# HIM.net
KiCad netlist of a schematic drawn in Altium Designer
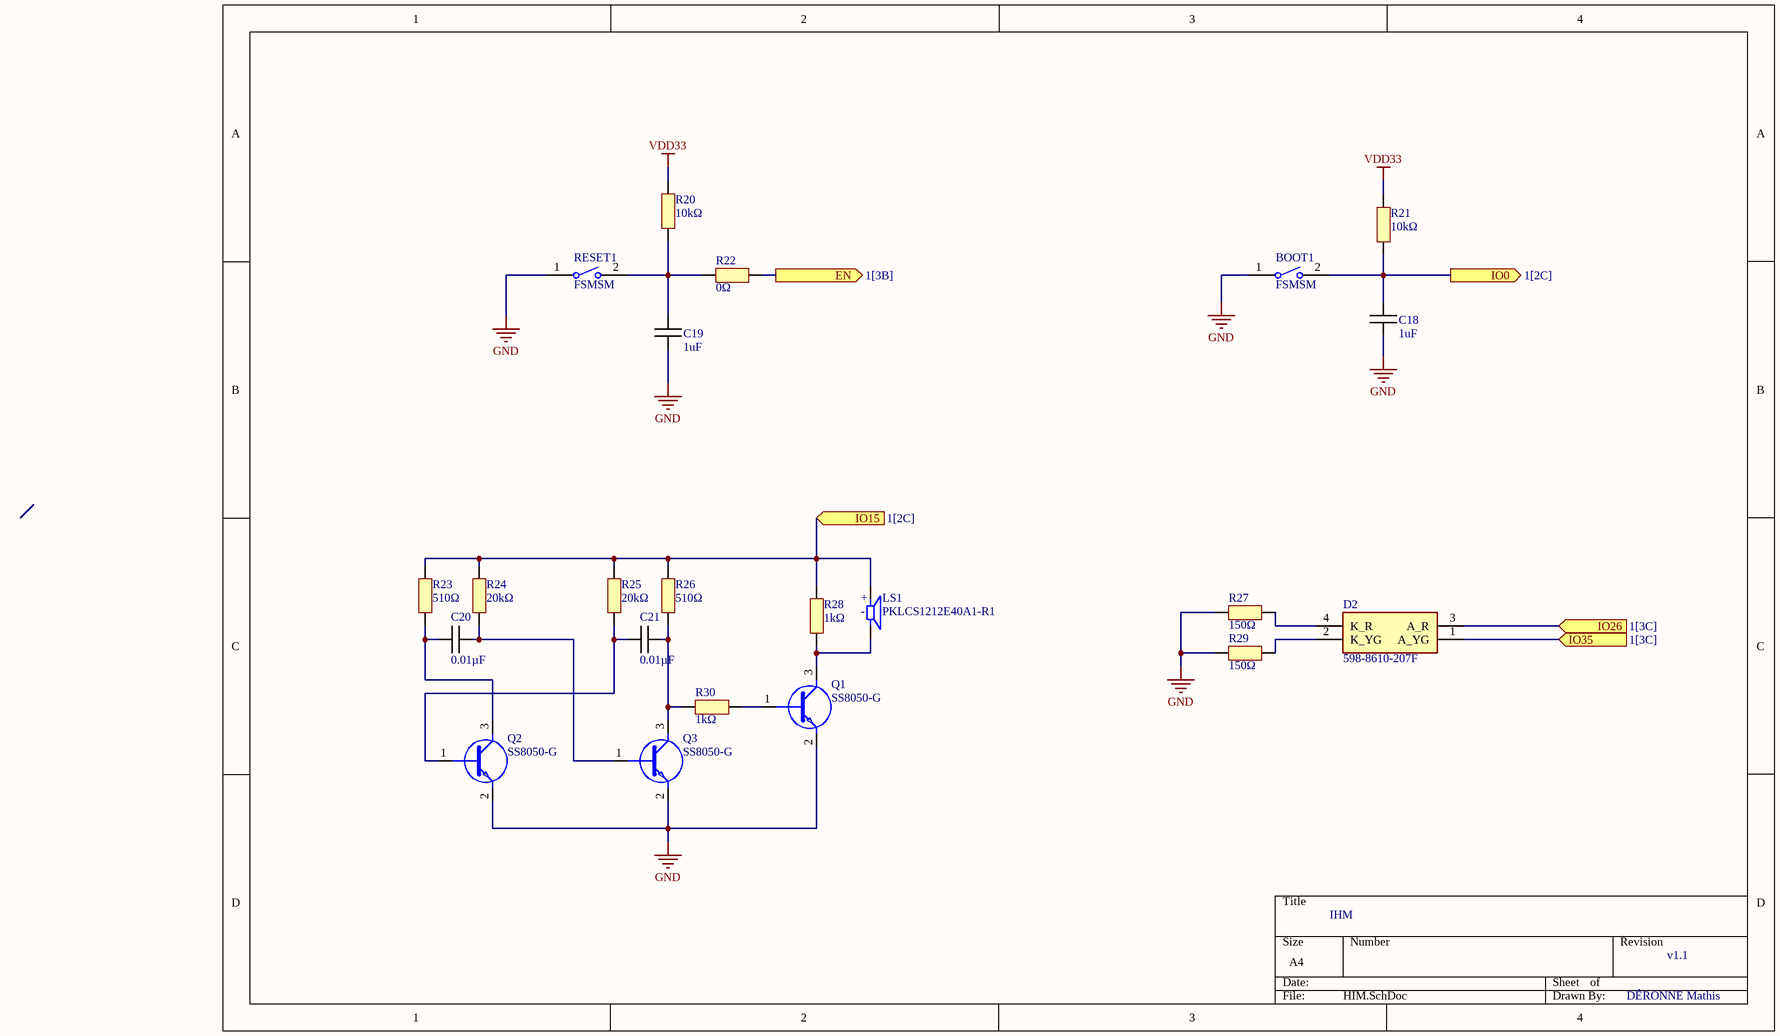
[diagram p0: HIM.SchDoc]

(export (version "E")
  (design (tool "Eeschema 10.0.6"))
  (components
    (comp (ref "BOOT1")
      (value "FSMSM")
      (footprint "TECO-FSMSM-2_V")
      (description "FSMSM Push Button Switch, 50 mA, -35 to 85 degC, 2-Pin SMD, RoHS, Bulk")
      (fields (field (name "MANUFACTURER") "TE Connectivity"))
      (libsource (lib "SCHLibrary") (part "CMP-2000-07511-1"))
    )
    (comp (ref "C18")
      (value "1uF")
      (footprint "CAPC1005X06N")
      (libsource (lib "SCHLibrary") (part "Capacitor"))
    )
    (comp (ref "C19")
      (value "1uF")
      (footprint "CAPC1005X06N")
      (libsource (lib "SCHLibrary") (part "Capacitor"))
    )
    (comp (ref "C20")
      (value "0.01µF")
      (footprint "CAPC1005X06N")
      (libsource (lib "SCHLibrary") (part "Capacitor"))
    )
    (comp (ref "C21")
      (value "0.01µF")
      (footprint "CAPC1005X06N")
      (libsource (lib "SCHLibrary") (part "Capacitor"))
    )
    (comp (ref "D2")
      (value "598-8610-207F")
      (footprint "5988610207F")
      (description "Standard LEDs - SMD Red/Green WC 80/50mcd 645/570nm")
      (fields (field (name "MOUSER PART NUMBER") "645-598-8610-207F"))
      (libsource (lib "SCHLibrary") (part "598-8610-207F"))
    )
    (comp (ref "LS1")
      (value "PKLCS1212E40A1-R1")
      (footprint "SPKR_PKLCS1212E40A1-R1")
      (description "Buzzers Transducer, Externally Driven Piezo 1.5V 2kHz 70dB @ 1.5V, 10cm Surface Mount Solder Pads")
      (fields (field (name "MF") "Murata Electronics"))
      (libsource (lib "SCHLibrary") (part "PKLCS1212E40A1-R1"))
    )
    (comp (ref "Q1")
      (value "SS8050-G")
      (footprint "SS8050-G")
      (description "Bipolar Transistors - BJT NPN TRANSISTOR 1.5A 40V")
      (libsource (lib "SCHLibrary") (part "SS8050-G"))
    )
    (comp (ref "Q2")
      (value "SS8050-G")
      (footprint "SS8050-G")
      (description "Bipolar Transistors - BJT NPN TRANSISTOR 1.5A 40V")
      (libsource (lib "SCHLibrary") (part "SS8050-G"))
    )
    (comp (ref "Q3")
      (value "SS8050-G")
      (footprint "SS8050-G")
      (description "Bipolar Transistors - BJT NPN TRANSISTOR 1.5A 40V")
      (libsource (lib "SCHLibrary") (part "SS8050-G"))
    )
    (comp (ref "R20")
      (value "10kΩ")
      (footprint "RESC1005X06N")
      (libsource (lib "SCHLibrary") (part "Resistor"))
    )
    (comp (ref "R21")
      (value "10kΩ")
      (footprint "RESC1005X06N")
      (libsource (lib "SCHLibrary") (part "Resistor"))
    )
    (comp (ref "R22") (value "0Ω") (footprint "RESC1005X06N") (libsource (lib "") (part "Resistor_1")))
    (comp (ref "R23")
      (value "510Ω")
      (footprint "RESC1005X06N")
      (libsource (lib "SCHLibrary") (part "Resistor"))
    )
    (comp (ref "R24")
      (value "20kΩ")
      (footprint "RESC1005X06N")
      (libsource (lib "SCHLibrary") (part "Resistor"))
    )
    (comp (ref "R25")
      (value "20kΩ")
      (footprint "RESC1005X06N")
      (libsource (lib "SCHLibrary") (part "Resistor"))
    )
    (comp (ref "R26")
      (value "510Ω")
      (footprint "RESC1005X06N")
      (libsource (lib "SCHLibrary") (part "Resistor"))
    )
    (comp (ref "R27") (value "150Ω") (footprint "RESC1005X06N") (libsource (lib "") (part "Resistor_1")))
    (comp (ref "R28")
      (value "1kΩ")
      (footprint "RESC1005X06N")
      (libsource (lib "SCHLibrary") (part "Resistor"))
    )
    (comp (ref "R29") (value "150Ω") (footprint "RESC1005X06N") (libsource (lib "") (part "Resistor_1")))
    (comp (ref "R30") (value "1kΩ") (footprint "RESC1005X06N") (libsource (lib "") (part "Resistor_1")))
    (comp (ref "RESET1")
      (value "FSMSM")
      (footprint "TECO-FSMSM-2_V")
      (description "FSMSM Push Button Switch, 50 mA, -35 to 85 degC, 2-Pin SMD, RoHS, Bulk")
      (fields (field (name "MANUFACTURER") "TE Connectivity"))
      (libsource (lib "SCHLibrary") (part "CMP-2000-07511-1"))
    )
  )
  (nets
    (net (code "1") (name "/EN") (class "Default")
      (node (ref "R22") (pin "2") (pinfunction "2_2") (pintype "passive"))
    )
    (net (code "2") (name "/IO0") (class "Default")
      (node (ref "BOOT1") (pin "2") (pinfunction "2_2") (pintype "passive"))
      (node (ref "C18") (pin "1") (pinfunction "1_1") (pintype "passive"))
      (node (ref "R21") (pin "1") (pinfunction "1_1") (pintype "passive"))
    )
    (net (code "3") (name "/IO15") (class "Default")
      (node (ref "LS1") (pin "P") (pinfunction "P_P") (pintype "passive"))
      (node (ref "R23") (pin "2") (pinfunction "2_2") (pintype "passive"))
      (node (ref "R24") (pin "2") (pinfunction "2_2") (pintype "passive"))
      (node (ref "R25") (pin "2") (pinfunction "2_2") (pintype "passive"))
      (node (ref "R26") (pin "2") (pinfunction "2_2") (pintype "passive"))
      (node (ref "R28") (pin "2") (pinfunction "2_2") (pintype "passive"))
    )
    (net (code "4") (name "/IO26") (class "Default")
      (node (ref "D2") (pin "3") (pinfunction "A_R_3") (pintype "passive"))
    )
    (net (code "5") (name "/IO35") (class "Default")
      (node (ref "D2") (pin "1") (pinfunction "A_YG_1") (pintype "passive"))
    )
    (net (code "6") (name "GND") (class "Default")
      (node (ref "BOOT1") (pin "1") (pinfunction "1_1") (pintype "passive"))
      (node (ref "C18") (pin "2") (pinfunction "2_2") (pintype "passive"))
      (node (ref "C19") (pin "2") (pinfunction "2_2") (pintype "passive"))
      (node (ref "Q1") (pin "2") (pinfunction "E_2") (pintype "passive"))
      (node (ref "Q2") (pin "2") (pinfunction "E_2") (pintype "passive"))
      (node (ref "Q3") (pin "2") (pinfunction "E_2") (pintype "passive"))
      (node (ref "R27") (pin "1") (pinfunction "1_1") (pintype "passive"))
      (node (ref "R29") (pin "1") (pinfunction "1_1") (pintype "passive"))
      (node (ref "RESET1") (pin "1") (pinfunction "1_1") (pintype "passive"))
    )
    (net (code "7") (name "Net-(C19-Pad1)") (class "Default")
      (node (ref "C19") (pin "1") (pinfunction "1_1") (pintype "passive"))
      (node (ref "R20") (pin "1") (pinfunction "1_1") (pintype "passive"))
      (node (ref "R22") (pin "1") (pinfunction "1_1") (pintype "passive"))
      (node (ref "RESET1") (pin "2") (pinfunction "2_2") (pintype "passive"))
    )
    (net (code "8") (name "Net-(D2-K_R)") (class "Default")
      (node (ref "D2") (pin "4") (pinfunction "K_R_4") (pintype "passive"))
      (node (ref "R27") (pin "2") (pinfunction "2_2") (pintype "passive"))
    )
    (net (code "9") (name "Net-(D2-K_YG)") (class "Default")
      (node (ref "D2") (pin "2") (pinfunction "K_YG_2") (pintype "passive"))
      (node (ref "R29") (pin "2") (pinfunction "2_2") (pintype "passive"))
    )
    (net (code "10") (name "Net-(Q1-B)") (class "Default")
      (node (ref "Q1") (pin "1") (pinfunction "B_1") (pintype "passive"))
      (node (ref "R30") (pin "2") (pinfunction "2_2") (pintype "passive"))
    )
    (net (code "11") (name "Net-(Q1-C)") (class "Default")
      (node (ref "LS1") (pin "N") (pinfunction "N_N") (pintype "passive"))
      (node (ref "Q1") (pin "3") (pinfunction "C_3") (pintype "passive"))
      (node (ref "R28") (pin "1") (pinfunction "1_1") (pintype "passive"))
    )
    (net (code "12") (name "Net-(Q2-B)") (class "Default")
      (node (ref "C21") (pin "1") (pinfunction "1_1") (pintype "passive"))
      (node (ref "Q2") (pin "1") (pinfunction "B_1") (pintype "passive"))
      (node (ref "R25") (pin "1") (pinfunction "1_1") (pintype "passive"))
    )
    (net (code "13") (name "Net-(Q2-C)") (class "Default")
      (node (ref "C20") (pin "1") (pinfunction "1_1") (pintype "passive"))
      (node (ref "Q2") (pin "3") (pinfunction "C_3") (pintype "passive"))
      (node (ref "R23") (pin "1") (pinfunction "1_1") (pintype "passive"))
    )
    (net (code "14") (name "Net-(Q3-B)") (class "Default")
      (node (ref "C20") (pin "2") (pinfunction "2_2") (pintype "passive"))
      (node (ref "Q3") (pin "1") (pinfunction "B_1") (pintype "passive"))
      (node (ref "R24") (pin "1") (pinfunction "1_1") (pintype "passive"))
    )
    (net (code "15") (name "Net-(Q3-C)") (class "Default")
      (node (ref "C21") (pin "2") (pinfunction "2_2") (pintype "passive"))
      (node (ref "Q3") (pin "3") (pinfunction "C_3") (pintype "passive"))
      (node (ref "R26") (pin "1") (pinfunction "1_1") (pintype "passive"))
      (node (ref "R30") (pin "1") (pinfunction "1_1") (pintype "passive"))
    )
    (net (code "16") (name "VDD33") (class "Default")
      (node (ref "R20") (pin "2") (pinfunction "2_2") (pintype "passive"))
      (node (ref "R21") (pin "2") (pinfunction "2_2") (pintype "passive"))
    )
  )
)
